# vusbtinyisp_through-hole.net
KiCad netlist of a schematic drawn in EAGLE
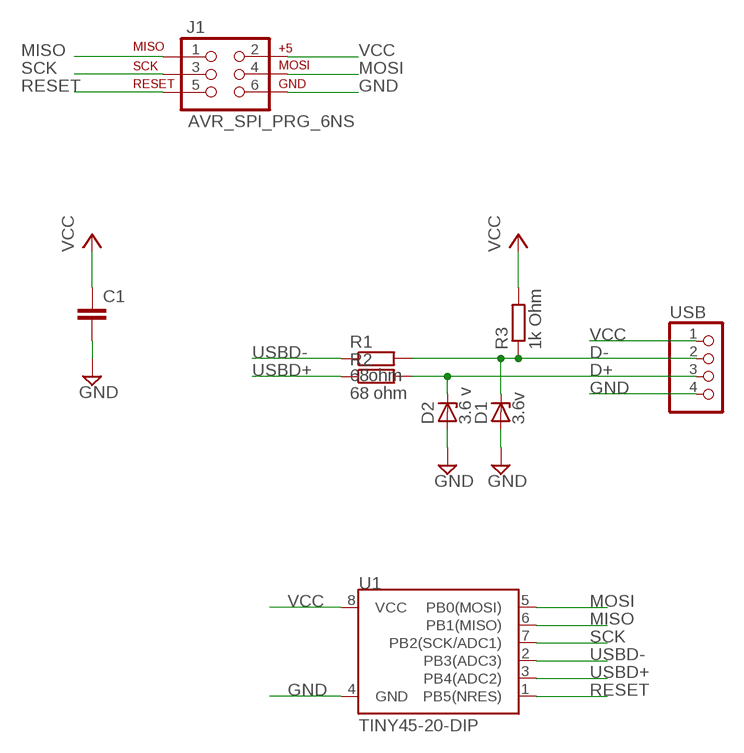
[diagram p0: schematic, sheet 1]

(export (version "E")
  (design (tool "Eeschema 10.0.6"))
  (components
    (comp (ref "C1")
      (value "CAPPTH")
      (footprint "eagle-import:CAP-PTH-SMALL")
      (libsource (lib "eagle-import") (part "CAPPTH"))
    )
    (comp (ref "D1")
      (value "3.6v")
      (footprint "eagle-import:DO35Z10")
      (libsource (lib "eagle-import") (part "ZENER-DIODEDO35Z10"))
    )
    (comp (ref "D2")
      (value "3.6 v")
      (footprint "eagle-import:DO35Z10")
      (libsource (lib "eagle-import") (part "ZENER-DIODEDO35Z10"))
    )
    (comp (ref "J1")
      (value "AVR_SPI_PRG_6NS")
      (footprint "eagle-import:2X3-NS")
      (libsource (lib "eagle-import") (part "AVR_SPI_PRG_6NS"))
    )
    (comp (ref "R1")
      (value "68ohm")
      (footprint "eagle-import:0207_10")
      (libsource (lib "eagle-import") (part "R-EU_0207/10"))
    )
    (comp (ref "R2")
      (value "68 ohm")
      (footprint "eagle-import:0207_10")
      (libsource (lib "eagle-import") (part "R-EU_0207/10"))
    )
    (comp (ref "R3")
      (value "1k Ohm")
      (footprint "eagle-import:0207_10")
      (libsource (lib "eagle-import") (part "R-EU_0207/10"))
    )
    (comp (ref "U1")
      (value "TINY45-20-DIP")
      (footprint "eagle-import:DIP08")
      (libsource (lib "eagle-import") (part "ATTINY45TINY45-20-DIP"))
    )
    (comp (ref "USB")
      (value "PINHD-1X4")
      (footprint "eagle-import:1X04")
      (libsource (lib "eagle-import") (part "PINHD-1X4"))
    )
  )
  (nets
    (net (code "1") (name "/D+") (class "Default")
      (node (ref "D2") (pin "C") (pinfunction "C_C") (pintype "passive"))
      (node (ref "R2") (pin "2") (pinfunction "2_2") (pintype "passive"))
      (node (ref "USB") (pin "3") (pinfunction "3_3") (pintype "passive"))
    )
    (net (code "2") (name "/D-") (class "Default")
      (node (ref "D1") (pin "C") (pinfunction "C_C") (pintype "passive"))
      (node (ref "R1") (pin "2") (pinfunction "2_2") (pintype "passive"))
      (node (ref "R3") (pin "1") (pinfunction "1_1") (pintype "passive"))
      (node (ref "USB") (pin "2") (pinfunction "2_2") (pintype "passive"))
    )
    (net (code "3") (name "/MISO") (class "Default")
      (node (ref "J1") (pin "1") (pinfunction "1_1") (pintype "passive"))
      (node (ref "U1") (pin "6") (pinfunction "PB1(MISO)_6") (pintype "bidirectional"))
    )
    (net (code "4") (name "/MOSI") (class "Default")
      (node (ref "J1") (pin "4") (pinfunction "4_4") (pintype "passive"))
      (node (ref "U1") (pin "5") (pinfunction "PB0(MOSI)_5") (pintype "bidirectional"))
    )
    (net (code "5") (name "/RESET") (class "Default")
      (node (ref "J1") (pin "5") (pinfunction "5_5") (pintype "passive"))
      (node (ref "U1") (pin "1") (pinfunction "PB5(NRES)_1") (pintype "bidirectional"))
    )
    (net (code "6") (name "/SCK") (class "Default")
      (node (ref "J1") (pin "3") (pinfunction "3_3") (pintype "passive"))
      (node (ref "U1") (pin "7") (pinfunction "PB2(SCK/ADC1)_7") (pintype "bidirectional"))
    )
    (net (code "7") (name "/USBD+") (class "Default")
      (node (ref "R2") (pin "1") (pinfunction "1_1") (pintype "passive"))
      (node (ref "U1") (pin "3") (pinfunction "PB4(ADC2)_3") (pintype "bidirectional"))
    )
    (net (code "8") (name "/USBD-") (class "Default")
      (node (ref "R1") (pin "1") (pinfunction "1_1") (pintype "passive"))
      (node (ref "U1") (pin "2") (pinfunction "PB3(ADC3)_2") (pintype "bidirectional"))
    )
    (net (code "9") (name "GND") (class "Default")
      (node (ref "C1") (pin "2") (pinfunction "2_2") (pintype "passive"))
      (node (ref "D1") (pin "A") (pinfunction "A_A") (pintype "passive"))
      (node (ref "D2") (pin "A") (pinfunction "A_A") (pintype "passive"))
      (node (ref "J1") (pin "6") (pinfunction "6_6") (pintype "passive"))
      (node (ref "U1") (pin "4") (pinfunction "GND_4") (pintype "bidirectional"))
      (node (ref "USB") (pin "4") (pinfunction "4_4") (pintype "passive"))
    )
    (net (code "10") (name "VCC") (class "Default")
      (node (ref "C1") (pin "1") (pinfunction "1_1") (pintype "passive"))
      (node (ref "J1") (pin "2") (pinfunction "2_2") (pintype "passive"))
      (node (ref "R3") (pin "2") (pinfunction "2_2") (pintype "passive"))
      (node (ref "U1") (pin "8") (pinfunction "VCC_8") (pintype "bidirectional"))
      (node (ref "USB") (pin "1") (pinfunction "1_1") (pintype "passive"))
    )
  )
)
